# input-port-con.net
KiCad netlist of a schematic drawn in Altium Designer
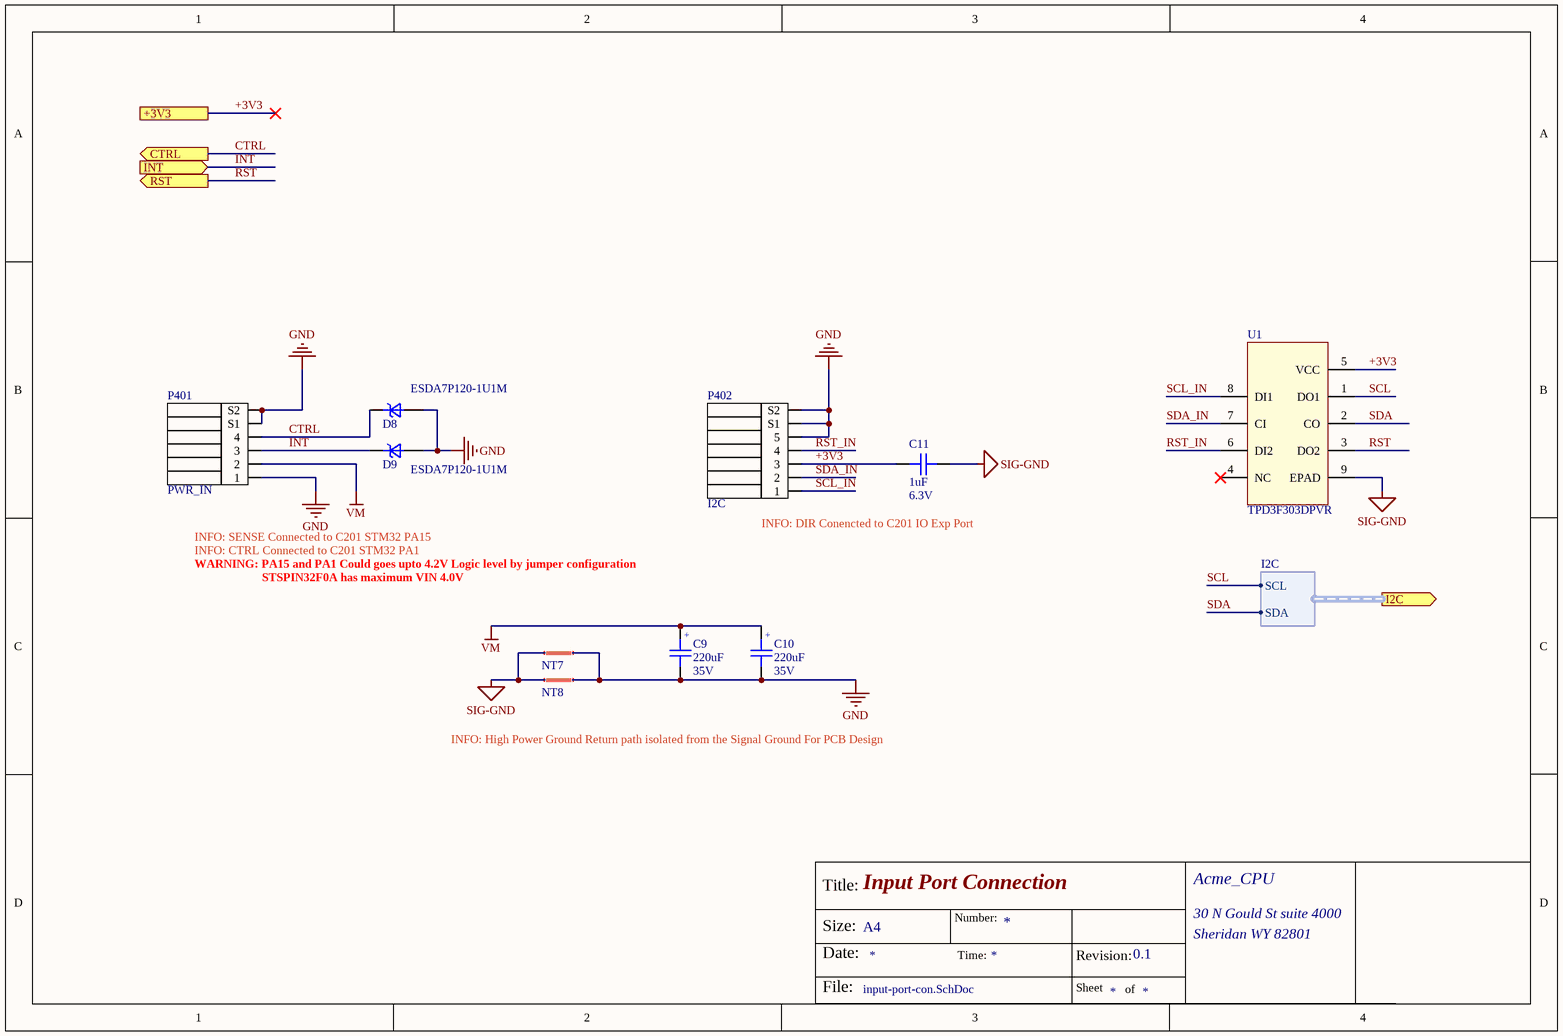
[diagram p0: input-port-con.SchDoc]

(export (version "E")
  (design (tool "Eeschema 10.0.6"))
  (components
    (comp (ref "C9")
      (value "CAP ALUM 220 UF 20% 35 V SMD")
      (footprint "WCAP-ASLI_D8H10.5")
      (description "220µF 35V Aluminum Electrolytic Capacitors Radial, Can - SMD  2000 Hrs @ 105°C")
      (fields
        (field (name "MANUFACTURER") "Wurth Elektronik")
        (field (name "MANUFACTURER PART NUMBER") "865080553014")
        (field (name "CAPACITANCE") "220uF")
        (field (name "RATED VOLTAGE") "35V")
      )
      (libsource (lib "d203-lib") (part "CAP ALUM 220 UF 20% 35 V SMD"))
    )
    (comp (ref "C10")
      (value "CAP ALUM 220 UF 20% 35 V SMD")
      (footprint "WCAP-ASLI_D8H10.5")
      (description "220µF 35V Aluminum Electrolytic Capacitors Radial, Can - SMD  2000 Hrs @ 105°C")
      (fields
        (field (name "MANUFACTURER") "Wurth Elektronik")
        (field (name "MANUFACTURER PART NUMBER") "865080553014")
        (field (name "CAPACITANCE") "220uF")
        (field (name "RATED VOLTAGE") "35V")
      )
      (libsource (lib "d203-lib") (part "CAP ALUM 220 UF 20% 35 V SMD"))
    )
    (comp (ref "C11")
      (value "CAP CER 1UF 6.3V X5R 0402")
      (footprint "C0402")
      (description "1µF ±10% 6.3V Ceramic Capacitor X5R 0402 (1005 Metric)")
      (fields
        (field (name "MANUFACTURER") "Yageo")
        (field (name "MANUFACTURER PART NUMBER") "CC0402KRX5R5BB105")
        (field (name "CAPACITANCE") "1uF")
        (field (name "VOLTAGE RATING") "6.3V")
      )
      (libsource (lib "capacitors_smd") (part "CAP CER 1UF 6.3V X5R 0402"))
    )
    (comp (ref "D8")
      (value "ESDA7P120-1U1M")
      (footprint "ST_QFN_1610")
      (description "11.5V Clamp 120A (8/20µs) Ipp Tvs Diode Surface Mount 1610")
      (fields (field (name "MANUFACTURER") "STMicroelectronics"))
      (libsource (lib "diodes_tvs") (part "TVS DIODE ESDA7P120-1U1M 5.5V 11.5V 1610"))
    )
    (comp (ref "D9")
      (value "ESDA7P120-1U1M")
      (footprint "ST_QFN_1610")
      (description "11.5V Clamp 120A (8/20µs) Ipp Tvs Diode Surface Mount 1610")
      (fields (field (name "MANUFACTURER") "STMicroelectronics"))
      (libsource (lib "diodes_tvs") (part "TVS DIODE ESDA7P120-1U1M 5.5V 11.5V 1610"))
    )
    (comp (ref "NT7")
      (value "Net Tie")
      (footprint "Net Tie 6x30mil")
      (libsource (lib "d203-lib") (part "Net Tie Line"))
    )
    (comp (ref "NT8")
      (value "Net Tie")
      (footprint "Net Tie 6x30mil")
      (libsource (lib "d203-lib") (part "Net Tie Line"))
    )
    (comp (ref "P401")
      (value "PWR_IN")
      (footprint "JST_S4B-ZR-SM4A-TF(LF)(SN)")
      (description "Connector Header SMD, Right Angle 4 position 0.059\" (1.50mm)")
      (fields (field (name "MANUFACTURER") "JST") (field (name "MANUFACTURER PART NUMBER") "S5B-ZR-SM4A-TF"))
      (libsource (lib "JST-ZR-v1.3") (part "JST_S4B-ZR-SM4A-TF(LF)(SN)"))
    )
    (comp (ref "P402")
      (value "I2C")
      (footprint "JST_S5B-ZR-SM4A-TF(LF)(SN)")
      (description "Connector Header SMD, Right Angle 4 position 0.059\" (1.50mm)")
      (fields (field (name "MANUFACTURER") "JST") (field (name "MANUFACTURER PART NUMBER") "S5B-ZR-SM4A-TF"))
      (libsource (lib "JST-ZR-v1.3") (part "JST_S5B-ZR-SM4A-TF(LF)(SN)"))
    )
    (comp (ref "U1")
      (value "TPD3F303DPVR")
      (footprint "DPV8_1P7X0P4")
      (description "RC (Pi) EMI Filter 2nd Order Low Pass 3 Channel R = 47Ohms, 100Ohms, C = 20pF  8-UFDFN Exposed Pad")
      (fields (field (name "MANUFACTURER") "Texas Instruments"))
      (libsource (lib "diodes_tvs") (part "FILTER RC(PI) ESD SMD  8-UFDFN EP"))
    )
  )
  (nets
    (net (code "2") (name "/+3V3") (class "Default")
      (node (ref "C11") (pin "2") (pinfunction "2_2") (pintype "passive"))
      (node (ref "P402") (pin "3") (pinfunction "3_3") (pintype "passive"))
      (node (ref "U1") (pin "5") (pinfunction "VCC_5") (pintype "power_in"))
    )
    (net (code "3") (name "/CTRL") (class "Default")
      (node (ref "D8") (pin "1") (pinfunction "K_1") (pintype "passive"))
      (node (ref "P401") (pin "4") (pinfunction "4_4") (pintype "passive"))
    )
    (net (code "4") (name "/INT") (class "Default")
      (node (ref "D9") (pin "1") (pinfunction "K_1") (pintype "passive"))
      (node (ref "P401") (pin "3") (pinfunction "3_3") (pintype "passive"))
    )
    (net (code "5") (name "/RST") (class "Default")
      (node (ref "U1") (pin "3") (pinfunction "DO2_3") (pintype "passive"))
    )
    (net (code "6") (name "/RST_IN") (class "Default")
      (node (ref "P402") (pin "4") (pinfunction "4_4") (pintype "passive"))
      (node (ref "U1") (pin "6") (pinfunction "DI2_6") (pintype "passive"))
    )
    (net (code "7") (name "/SCL") (class "Default")
      (node (ref "U1") (pin "1") (pinfunction "DO1_1") (pintype "passive"))
    )
    (net (code "8") (name "/SCL_IN") (class "Default")
      (node (ref "P402") (pin "1") (pinfunction "1_1") (pintype "passive"))
      (node (ref "U1") (pin "8") (pinfunction "DI1_8") (pintype "passive"))
    )
    (net (code "9") (name "/SDA") (class "Default")
      (node (ref "U1") (pin "2") (pinfunction "CO_2") (pintype "passive"))
    )
    (net (code "10") (name "/SDA_IN") (class "Default")
      (node (ref "P402") (pin "2") (pinfunction "2_2") (pintype "passive"))
      (node (ref "U1") (pin "7") (pinfunction "CI_7") (pintype "passive"))
    )
    (net (code "12") (name "GND") (class "Default")
      (node (ref "C10") (pin "2") (pinfunction "2_2") (pintype "passive"))
      (node (ref "C9") (pin "2") (pinfunction "2_2") (pintype "passive"))
      (node (ref "D8") (pin "2") (pinfunction "A_2") (pintype "passive"))
      (node (ref "D9") (pin "2") (pinfunction "A_2") (pintype "passive"))
      (node (ref "NT7") (pin "2") (pintype "passive"))
      (node (ref "NT8") (pin "2") (pintype "passive"))
      (node (ref "P401") (pin "1") (pinfunction "1_1") (pintype "passive"))
      (node (ref "P401") (pin "S1") (pinfunction "S1_S1") (pintype "passive"))
      (node (ref "P401") (pin "S2") (pinfunction "S2_S2") (pintype "passive"))
      (node (ref "P402") (pin "5") (pinfunction "5_5") (pintype "passive"))
      (node (ref "P402") (pin "S1") (pinfunction "S1_S1") (pintype "passive"))
      (node (ref "P402") (pin "S2") (pinfunction "S2_S2") (pintype "passive"))
    )
    (net (code "13") (name "SIG-GND") (class "Default")
      (node (ref "C11") (pin "1") (pinfunction "1_1") (pintype "passive"))
      (node (ref "NT7") (pin "1") (pintype "passive"))
      (node (ref "NT8") (pin "1") (pintype "passive"))
      (node (ref "U1") (pin "9") (pinfunction "EPAD_9") (pintype "passive"))
    )
    (net (code "14") (name "VM") (class "Default")
      (node (ref "C10") (pin "1") (pinfunction "1_1") (pintype "passive"))
      (node (ref "C9") (pin "1") (pinfunction "1_1") (pintype "passive"))
      (node (ref "P401") (pin "2") (pinfunction "2_2") (pintype "passive"))
    )
    (net (code "15") (name "unconnected-(U1-NC-Pad4)") (class "Default")
      (node (ref "U1") (pin "4") (pinfunction "NC_4") (pintype "passive+no_connect"))
    )
  )
)
